# openmv.net
KiCad netlist of a schematic drawn in EAGLE
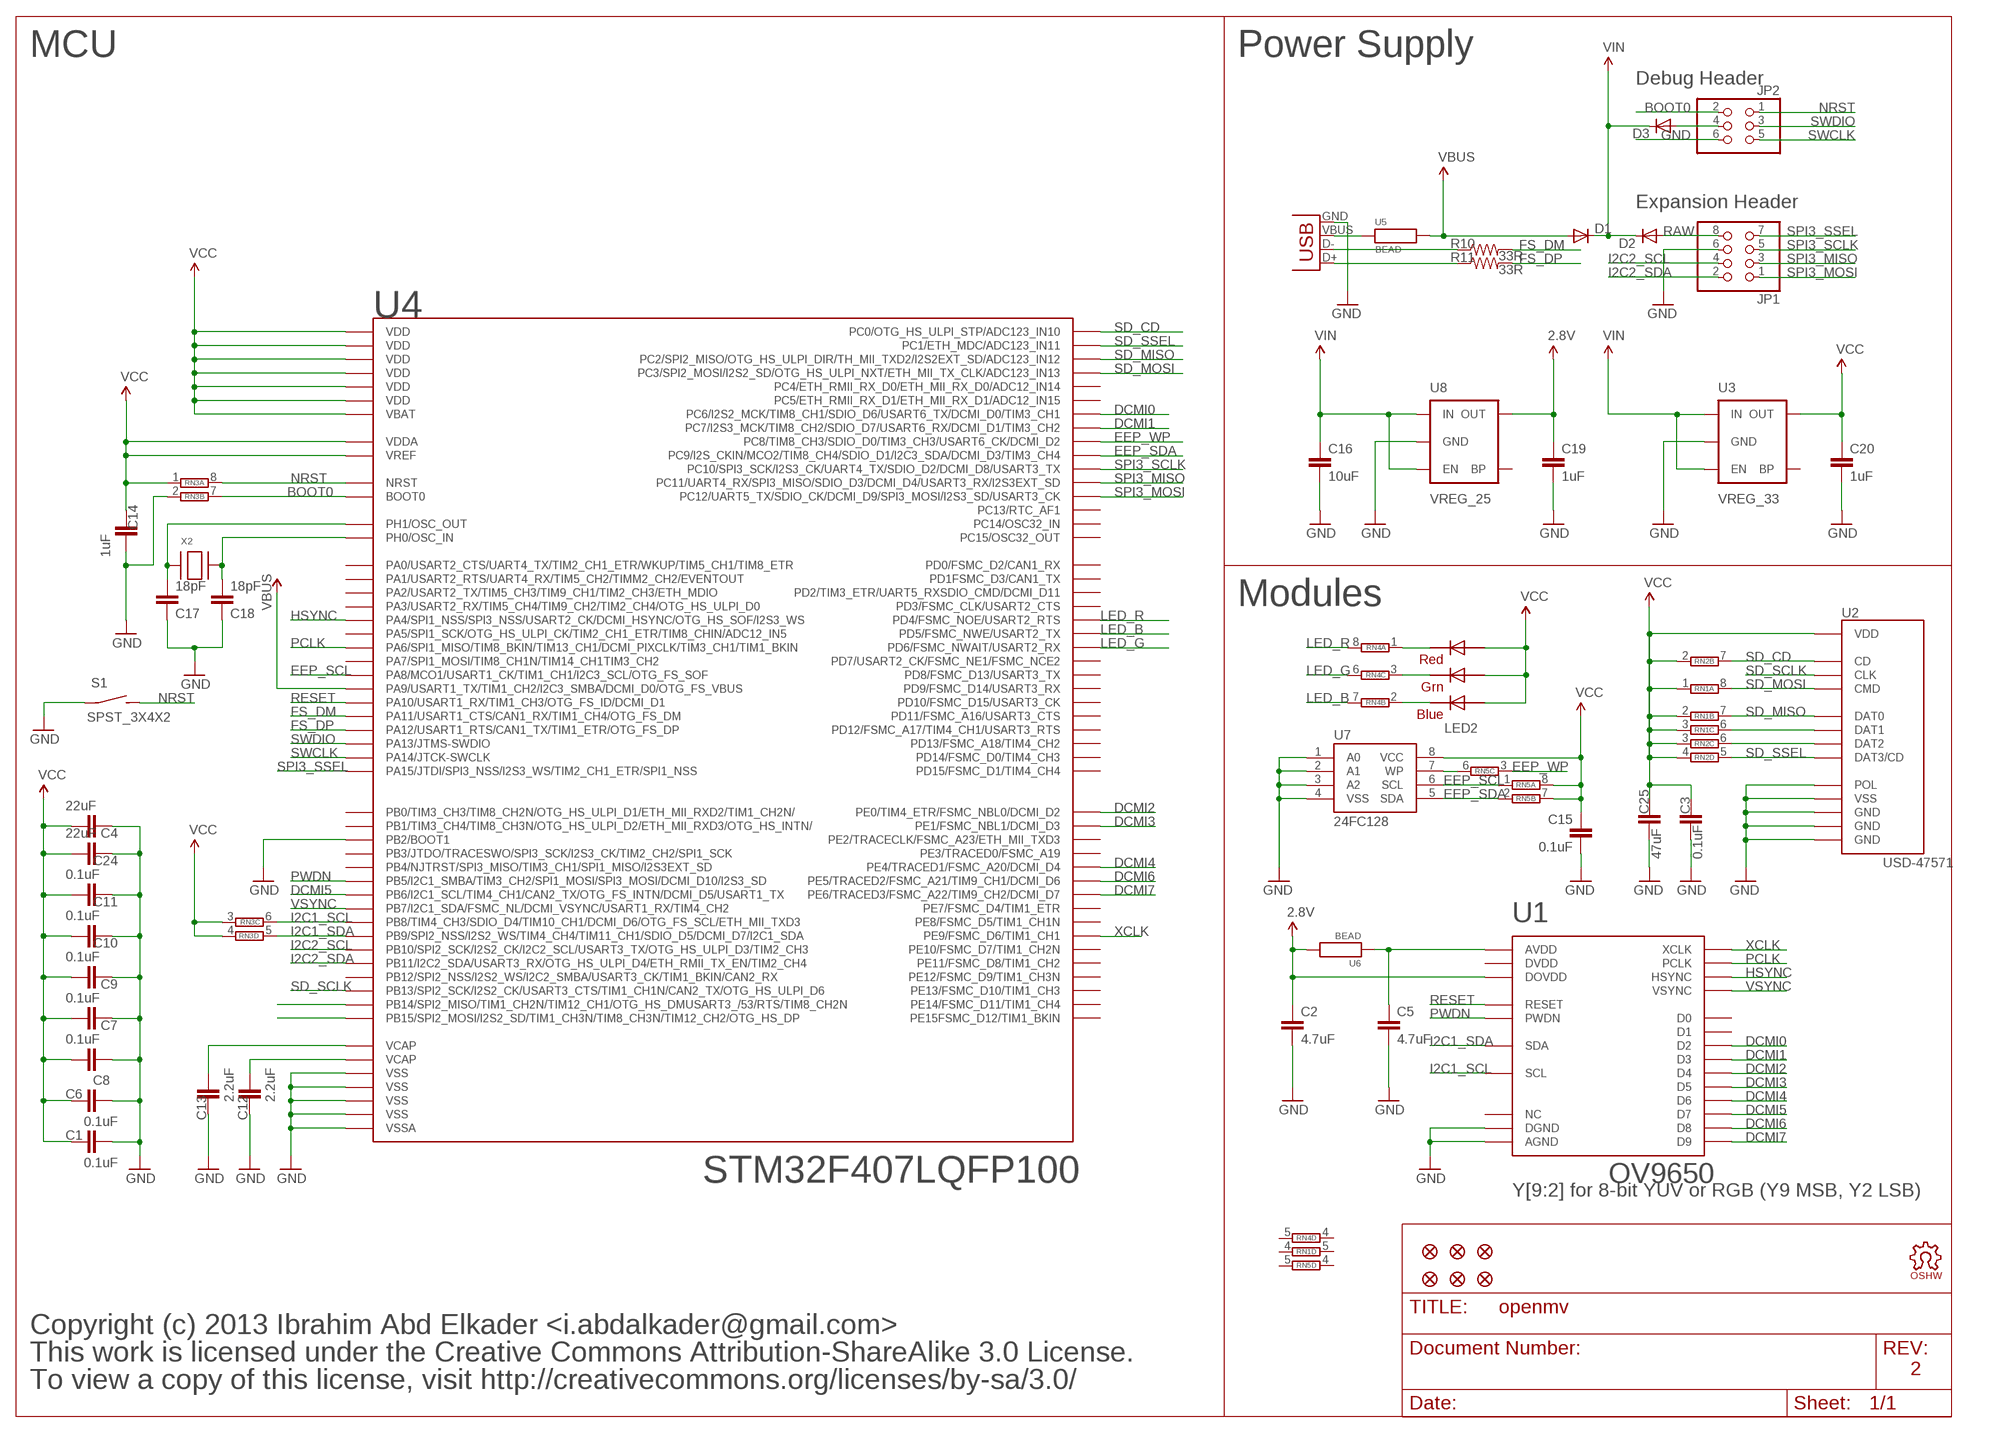
[diagram p0: schematic, sheet 1]

(export (version "E")
  (design (tool "Eeschema 10.0.6"))
  (components
    (comp (ref "C1")
      (value "0.1uF")
      (footprint "eagle-import:0402-CAP")
      (libsource (lib "eagle-import") (part "CAP0402-CAP"))
    )
    (comp (ref "C2")
      (value "4.7uF")
      (footprint "eagle-import:0402-CAP")
      (libsource (lib "eagle-import") (part "CAP0402-CAP"))
    )
    (comp (ref "C3")
      (value "0.1uF")
      (footprint "eagle-import:0402-CAP")
      (libsource (lib "eagle-import") (part "CAP0402-CAP"))
    )
    (comp (ref "C4")
      (value "22uF")
      (footprint "eagle-import:0805")
      (libsource (lib "eagle-import") (part "CAP0805"))
    )
    (comp (ref "C5")
      (value "4.7uF")
      (footprint "eagle-import:0402-CAP")
      (libsource (lib "eagle-import") (part "CAP0402-CAP"))
    )
    (comp (ref "C6")
      (value "0.1uF")
      (footprint "eagle-import:0402-CAP")
      (libsource (lib "eagle-import") (part "CAP0402-CAP"))
    )
    (comp (ref "C7")
      (value "0.1uF")
      (footprint "eagle-import:0402-CAP")
      (libsource (lib "eagle-import") (part "CAP0402-CAP"))
    )
    (comp (ref "C8")
      (value "0.1uF")
      (footprint "eagle-import:0402-CAP")
      (libsource (lib "eagle-import") (part "CAP0402-CAP"))
    )
    (comp (ref "C9")
      (value "0.1uF")
      (footprint "eagle-import:0402-CAP")
      (libsource (lib "eagle-import") (part "CAP0402-CAP"))
    )
    (comp (ref "C10")
      (value "0.1uF")
      (footprint "eagle-import:0402-CAP")
      (libsource (lib "eagle-import") (part "CAP0402-CAP"))
    )
    (comp (ref "C11")
      (value "0.1uF")
      (footprint "eagle-import:0402-CAP")
      (libsource (lib "eagle-import") (part "CAP0402-CAP"))
    )
    (comp (ref "C12")
      (value "2.2uF")
      (footprint "eagle-import:0402-CAP")
      (libsource (lib "eagle-import") (part "CAP0402-CAP"))
    )
    (comp (ref "C13")
      (value "2.2uF")
      (footprint "eagle-import:0402-CAP")
      (libsource (lib "eagle-import") (part "CAP0402-CAP"))
    )
    (comp (ref "C14")
      (value "1uF")
      (footprint "eagle-import:0402-CAP")
      (libsource (lib "eagle-import") (part "CAP0402-CAP"))
    )
    (comp (ref "C15")
      (value "0.1uF")
      (footprint "eagle-import:0402-CAP")
      (libsource (lib "eagle-import") (part "CAP0402-CAP"))
    )
    (comp (ref "C16")
      (value "10uF")
      (footprint "eagle-import:0805")
      (libsource (lib "eagle-import") (part "CAP0805"))
    )
    (comp (ref "C17")
      (value "18pF")
      (footprint "eagle-import:0402-CAP")
      (libsource (lib "eagle-import") (part "CAP0402-CAP"))
    )
    (comp (ref "C18")
      (value "18pF")
      (footprint "eagle-import:0402-CAP")
      (libsource (lib "eagle-import") (part "CAP0402-CAP"))
    )
    (comp (ref "C19")
      (value "1uF")
      (footprint "eagle-import:0402-CAP")
      (libsource (lib "eagle-import") (part "CAP0402-CAP"))
    )
    (comp (ref "C20")
      (value "1uF")
      (footprint "eagle-import:0402-CAP")
      (libsource (lib "eagle-import") (part "CAP0402-CAP"))
    )
    (comp (ref "C24")
      (value "22uF")
      (footprint "eagle-import:0805")
      (libsource (lib "eagle-import") (part "CAP0805"))
    )
    (comp (ref "C25")
      (value "47uF")
      (footprint "eagle-import:0805")
      (libsource (lib "eagle-import") (part "CAP0805"))
    )
    (comp (ref "D1")
      (value "DIODESOD")
      (footprint "eagle-import:SOD-323")
      (libsource (lib "eagle-import") (part "DIODESOD"))
    )
    (comp (ref "D2")
      (value "DIODESOD")
      (footprint "eagle-import:SOD-323")
      (libsource (lib "eagle-import") (part "DIODESOD"))
    )
    (comp (ref "D3")
      (value "DIODESOD")
      (footprint "eagle-import:SOD-323")
      (libsource (lib "eagle-import") (part "DIODESOD"))
    )
    (comp (ref "JP1")
      (value "PINHD-2X4")
      (footprint "eagle-import:2X04")
      (libsource (lib "eagle-import") (part "PINHD-2X4"))
    )
    (comp (ref "JP2")
      (value "PINHD-2X3")
      (footprint "eagle-import:2X03")
      (libsource (lib "eagle-import") (part "PINHD-2X3"))
    )
    (comp (ref "JP3")
      (value "FIDUCIAL1X2")
      (footprint "eagle-import:FIDUCIAL-1X2")
      (libsource (lib "eagle-import") (part "FIDUCIAL1X2"))
    )
    (comp (ref "JP4")
      (value "FIDUCIAL1X2")
      (footprint "eagle-import:FIDUCIAL-1X2")
      (libsource (lib "eagle-import") (part "FIDUCIAL1X2"))
    )
    (comp (ref "JP5")
      (value "FIDUCIAL1X2")
      (footprint "eagle-import:FIDUCIAL-1X2")
      (libsource (lib "eagle-import") (part "FIDUCIAL1X2"))
    )
    (comp (ref "JP6")
      (value "FIDUCIAL1X2")
      (footprint "eagle-import:FIDUCIAL-1X2")
      (libsource (lib "eagle-import") (part "FIDUCIAL1X2"))
    )
    (comp (ref "JP7")
      (value "FIDUCIAL1X2")
      (footprint "eagle-import:FIDUCIAL-1X2")
      (libsource (lib "eagle-import") (part "FIDUCIAL1X2"))
    )
    (comp (ref "JP8")
      (value "FIDUCIAL1X2")
      (footprint "eagle-import:FIDUCIAL-1X2")
      (libsource (lib "eagle-import") (part "FIDUCIAL1X2"))
    )
    (comp (ref "LED2")
      (value "RGBLED5050")
      (footprint "eagle-import:RGBLED5050")
      (libsource (lib "eagle-import") (part "RGBLED5050"))
    )
    (comp (ref "LOGO1")
      (value "OSHW_LOGO_FILLX0150-NT")
      (footprint "eagle-import:OSHW_FILLX150_NOTEXT")
      (libsource (lib "eagle-import") (part "OSHW_LOGO_FILLX0150-NT"))
    )
    (comp (ref "R10")
      (value "33R")
      (footprint "eagle-import:0402-RES")
      (libsource (lib "eagle-import") (part "RESISTOR0402-RES"))
    )
    (comp (ref "R11")
      (value "33R")
      (footprint "eagle-import:0402-RES")
      (libsource (lib "eagle-import") (part "RESISTOR0402-RES"))
    )
    (comp (ref "RN1")
      (value "4R-NCAT16")
      (footprint "eagle-import:CAT16")
      (fields (field (name "OC_FARNELL") "unknown") (field (name "OC_NEWARK") "unknown"))
      (libsource (lib "eagle-import") (part "4R-NCAT16"))
    )
    (comp (ref "RN2")
      (value "4R-NCAT16")
      (footprint "eagle-import:CAT16")
      (fields (field (name "OC_FARNELL") "unknown") (field (name "OC_NEWARK") "unknown"))
      (libsource (lib "eagle-import") (part "4R-NCAT16"))
    )
    (comp (ref "RN3")
      (value "4R-NCAT16")
      (footprint "eagle-import:CAT16")
      (libsource (lib "eagle-import") (part "4R-NCAT16"))
    )
    (comp (ref "RN4")
      (value "4R-NCAT16")
      (footprint "eagle-import:CAT16")
      (fields (field (name "OC_FARNELL") "unknown") (field (name "OC_NEWARK") "unknown"))
      (libsource (lib "eagle-import") (part "4R-NCAT16"))
    )
    (comp (ref "RN5")
      (value "4R-NCAT16")
      (footprint "eagle-import:CAT16")
      (fields (field (name "OC_FARNELL") "unknown") (field (name "OC_NEWARK") "unknown"))
      (libsource (lib "eagle-import") (part "4R-NCAT16"))
    )
    (comp (ref "S1")
      (value "SPST_3X4X2")
      (footprint "eagle-import:3X4X2TACT")
      (libsource (lib "eagle-import") (part "SPST_3X4X2"))
    )
    (comp (ref "U1")
      (value "OV9650")
      (footprint "eagle-import:OV9650")
      (libsource (lib "eagle-import") (part "OV9650"))
    )
    (comp (ref "U2")
      (value "USD-47571")
      (footprint "eagle-import:USD-47571")
      (libsource (lib "eagle-import") (part "USD-47571"))
    )
    (comp (ref "U3")
      (value "VREG_33")
      (footprint "eagle-import:SOT23-5")
      (libsource (lib "eagle-import") (part "V_REG_LDOSMD"))
    )
    (comp (ref "U4")
      (value "STM32F407LQFP100")
      (footprint "eagle-import:LQFP100")
      (libsource (lib "eagle-import") (part "STM32F407LQFP100"))
    )
    (comp (ref "U5")
      (value "BEAD")
      (footprint "eagle-import:0402-CAP")
      (libsource (lib "eagle-import") (part "BEAD"))
    )
    (comp (ref "U6")
      (value "BEAD")
      (footprint "eagle-import:0402-CAP")
      (libsource (lib "eagle-import") (part "BEAD"))
    )
    (comp (ref "U7")
      (value "24FC128")
      (footprint "eagle-import:MSOP8")
      (libsource (lib "eagle-import") (part "24FC128"))
    )
    (comp (ref "U8")
      (value "VREG_25")
      (footprint "eagle-import:SOT23-5")
      (libsource (lib "eagle-import") (part "V_REG_LDOSMD"))
    )
    (comp (ref "X1")
      (value "USB-MICROB")
      (footprint "eagle-import:USB-MICROB")
      (libsource (lib "eagle-import") (part "USB-MICROB"))
    )
    (comp (ref "X2")
      (value "XTALNX5032")
      (footprint "eagle-import:NX5032")
      (libsource (lib "eagle-import") (part "XTALNX5032"))
    )
  )
  (nets
    (net (code "1") (name "/BOOT0") (class "Default")
      (node (ref "JP2") (pin "2") (pinfunction "2_2") (pintype "passive"))
      (node (ref "RN3") (pin "7") (pinfunction "2_7") (pintype "passive"))
      (node (ref "U4") (pin "94") (pinfunction "BOOT0_94") (pintype "bidirectional"))
    )
    (net (code "2") (name "/DCMI0") (class "Default")
      (node (ref "U1") (pin "P$19") (pinfunction "D2_P$19") (pintype "bidirectional"))
      (node (ref "U4") (pin "63") (pinfunction "PC6/I2S2_MCK/TIM8_CH1/SDIO_D6/USART6_TX/DCMI_D0/TIM3_CH1_63") (pintype "bidirectional"))
    )
    (net (code "3") (name "/DCMI1") (class "Default")
      (node (ref "U1") (pin "P$21") (pinfunction "D3_P$21") (pintype "bidirectional"))
      (node (ref "U4") (pin "64") (pinfunction "PC7/I2S3_MCK/TIM8_CH2/SDIO_D7/USART6_RX/DCMI_D1/TIM3_CH2_64") (pintype "bidirectional"))
    )
    (net (code "4") (name "/DCMI2") (class "Default")
      (node (ref "U1") (pin "P$22") (pinfunction "D4_P$22") (pintype "bidirectional"))
      (node (ref "U4") (pin "97") (pinfunction "PE0/TIM4_ETR/FSMC_NBL0/DCMI_D2_97") (pintype "bidirectional"))
    )
    (net (code "5") (name "/DCMI3") (class "Default")
      (node (ref "U1") (pin "P$20") (pinfunction "D5_P$20") (pintype "bidirectional"))
      (node (ref "U4") (pin "98") (pinfunction "PE1/FSMC_NBL1/DCMI_D3_98") (pintype "bidirectional"))
    )
    (net (code "6") (name "/DCMI4") (class "Default")
      (node (ref "U1") (pin "P$18") (pinfunction "D6_P$18") (pintype "bidirectional"))
      (node (ref "U4") (pin "3") (pinfunction "PE4/TRACED1/FSMC_A20/DCMI_D4_3") (pintype "bidirectional"))
    )
    (net (code "7") (name "/DCMI5") (class "Default")
      (node (ref "U1") (pin "P$16") (pinfunction "D7_P$16") (pintype "bidirectional"))
      (node (ref "U4") (pin "92") (pinfunction "PB6/I2C1_SCL/TIM4_CH1/CAN2_TX/OTG_FS_INTN/DCMI_D5/USART1_TX_92") (pintype "bidirectional"))
    )
    (net (code "8") (name "/DCMI6") (class "Default")
      (node (ref "U1") (pin "P$14") (pinfunction "D8_P$14") (pintype "bidirectional"))
      (node (ref "U4") (pin "4") (pinfunction "PE5/TRACED2/FSMC_A21/TIM9_CH1/DCMI_D6_4") (pintype "bidirectional"))
    )
    (net (code "9") (name "/DCMI7") (class "Default")
      (node (ref "U1") (pin "P$12") (pinfunction "D9_P$12") (pintype "bidirectional"))
      (node (ref "U4") (pin "5") (pinfunction "PE6/TRACED3/FSMC_A22/TIM9_CH2/DCMI_D7_5") (pintype "bidirectional"))
    )
    (net (code "10") (name "/EEP_SCL") (class "Default")
      (node (ref "RN5") (pin "1") (pinfunction "1_1") (pintype "passive"))
      (node (ref "U4") (pin "67") (pinfunction "PA8/MCO1/USART1_CK/TIM1_CH1/I2C3_SCL/OTG_FS_SOF_67") (pintype "bidirectional"))
      (node (ref "U7") (pin "6") (pinfunction "SCL_6") (pintype "bidirectional"))
    )
    (net (code "11") (name "/EEP_SDA") (class "Default")
      (node (ref "RN5") (pin "2") (pinfunction "1_2") (pintype "passive"))
      (node (ref "U4") (pin "66") (pinfunction "PC9/I2S_CKIN/MCO2/TIM8_CH4/SDIO_D1/I2C3_SDA/DCMI_D3/TIM3_CH4_66") (pintype "bidirectional"))
      (node (ref "U7") (pin "5") (pinfunction "SDA_5") (pintype "bidirectional"))
    )
    (net (code "12") (name "/EEP_WP") (class "Default")
      (node (ref "RN5") (pin "3") (pinfunction "1_3") (pintype "passive"))
      (node (ref "U4") (pin "65") (pinfunction "PC8/TIM8_CH3/SDIO_D0/TIM3_CH3/USART6_CK/DCMI_D2_65") (pintype "bidirectional"))
    )
    (net (code "13") (name "/FS_DM") (class "Default")
      (node (ref "R10") (pin "2") (pinfunction "2_2") (pintype "passive"))
      (node (ref "U4") (pin "70") (pinfunction "PA11/USART1_CTS/CAN1_RX/TIM1_CH4/OTG_FS_DM_70") (pintype "bidirectional"))
    )
    (net (code "14") (name "/FS_DP") (class "Default")
      (node (ref "R11") (pin "2") (pinfunction "2_2") (pintype "passive"))
      (node (ref "U4") (pin "71") (pinfunction "PA12/USART1_RTS/CAN1_TX/TIM1_ETR/OTG_FS_DP_71") (pintype "bidirectional"))
    )
    (net (code "15") (name "/HSYNC") (class "Default")
      (node (ref "U1") (pin "P$9") (pinfunction "HSYNC_P$9") (pintype "bidirectional"))
      (node (ref "U4") (pin "29") (pinfunction "PA4/SPI1_NSS/SPI3_NSS/USART2_CK/DCMI_HSYNC/OTG_HS_SOF/I2S3_WS_29") (pintype "bidirectional"))
    )
    (net (code "16") (name "/I2C1_SCL") (class "Default")
      (node (ref "RN3") (pin "6") (pinfunction "2_6") (pintype "passive"))
      (node (ref "U1") (pin "P$5") (pinfunction "SCL_P$5") (pintype "bidirectional"))
      (node (ref "U4") (pin "95") (pinfunction "PB8/TIM4_CH3/SDIO_D4/TIM10_CH1/DCMI_D6/OTG_FS_SCL/ETH_MII_TXD3_95") (pintype "bidirectional"))
    )
    (net (code "17") (name "/I2C1_SDA") (class "Default")
      (node (ref "RN3") (pin "5") (pinfunction "2_5") (pintype "passive"))
      (node (ref "U1") (pin "P$3") (pinfunction "SDA_P$3") (pintype "bidirectional"))
      (node (ref "U4") (pin "96") (pinfunction "PB9/SPI2_NSS/I2S2_WS/TIM4_CH4/TIM11_CH1/SDIO_D5/DCMI_D7/I2C1_SDA_96") (pintype "bidirectional"))
    )
    (net (code "18") (name "/I2C2_SCL") (class "Default")
      (node (ref "JP1") (pin "4") (pinfunction "4_4") (pintype "passive"))
      (node (ref "U4") (pin "47") (pinfunction "PB10/SPI2_SCK/I2S2_CK/I2C2_SCL/USART3_TX/OTG_HS_ULPI_D3/TIM2_CH3_47") (pintype "bidirectional"))
    )
    (net (code "19") (name "/I2C2_SDA") (class "Default")
      (node (ref "JP1") (pin "2") (pinfunction "2_2") (pintype "passive"))
      (node (ref "U4") (pin "48") (pinfunction "PB11/I2C2_SDA/USART3_RX/OTG_HS_ULPI_D4/ETH_RMII_TX_EN/TIM2_CH4_48") (pintype "bidirectional"))
    )
    (net (code "20") (name "/LED_B") (class "Default")
      (node (ref "RN4") (pin "7") (pinfunction "2_7") (pintype "passive"))
      (node (ref "U4") (pin "86") (pinfunction "PD5/FSMC_NWE/USART2_TX_86") (pintype "bidirectional"))
    )
    (net (code "21") (name "/LED_G") (class "Default")
      (node (ref "RN4") (pin "6") (pinfunction "2_6") (pintype "passive"))
      (node (ref "U4") (pin "87") (pinfunction "PD6/FSMC_NWAIT/USART2_RX_87") (pintype "bidirectional"))
    )
    (net (code "22") (name "/LED_R") (class "Default")
      (node (ref "RN4") (pin "8") (pinfunction "2_8") (pintype "passive"))
      (node (ref "U4") (pin "85") (pinfunction "PD4/FSMC_NOE/USART2_RTS_85") (pintype "bidirectional"))
    )
    (net (code "23") (name "/NRST") (class "Default")
      (node (ref "JP2") (pin "1") (pinfunction "1_1") (pintype "passive"))
      (node (ref "RN3") (pin "8") (pinfunction "2_8") (pintype "passive"))
      (node (ref "S1") (pin "P$2") (pinfunction "S_P$2") (pintype "passive"))
      (node (ref "U4") (pin "14") (pinfunction "NRST_14") (pintype "bidirectional"))
    )
    (net (code "24") (name "/PCLK") (class "Default")
      (node (ref "U1") (pin "P$17") (pinfunction "PCLK_P$17") (pintype "bidirectional"))
      (node (ref "U4") (pin "31") (pinfunction "PA6/SPI1_MISO/TIM8_BKIN/TIM13_CH1/DCMI_PIXCLK/TIM3_CH1/TIM1_BKIN_31") (pintype "bidirectional"))
    )
    (net (code "25") (name "/PWDN") (class "Default")
      (node (ref "U1") (pin "P$8") (pinfunction "PWDN_P$8") (pintype "bidirectional"))
      (node (ref "U4") (pin "91") (pinfunction "PB5/I2C1_SMBA/TIM3_CH2/SPI1_MOSI/SPI3_MOSI/DCMI_D10/I2S3_SD_91") (pintype "bidirectional"))
    )
    (net (code "26") (name "/RAW") (class "Default")
      (node (ref "D2") (pin "2") (pinfunction "A_2") (pintype "passive"))
      (node (ref "JP1") (pin "8") (pinfunction "8_8") (pintype "passive"))
    )
    (net (code "27") (name "/RESET") (class "Default")
      (node (ref "U1") (pin "P$6") (pinfunction "RESET_P$6") (pintype "bidirectional"))
      (node (ref "U4") (pin "69") (pinfunction "PA10/USART1_RX/TIM1_CH3/OTG_FS_ID/DCMI_D1_69") (pintype "bidirectional"))
    )
    (net (code "28") (name "/SD_CD") (class "Default")
      (node (ref "RN2") (pin "7") (pinfunction "2_7") (pintype "passive"))
      (node (ref "U2") (pin "G$5") (pinfunction "CD_G$5") (pintype "power_in"))
      (node (ref "U4") (pin "15") (pinfunction "PC0/OTG_HS_ULPI_STP/ADC123_IN10_15") (pintype "bidirectional"))
    )
    (net (code "29") (name "/SD_MISO") (class "Default")
      (node (ref "RN1") (pin "7") (pinfunction "2_7") (pintype "passive"))
      (node (ref "U2") (pin "P$7") (pinfunction "DAT0_P$7") (pintype "bidirectional"))
      (node (ref "U4") (pin "17") (pinfunction "PC2/SPI2_MISO/OTG_HS_ULPI_DIR/TH_MII_TXD2/I2S2EXT_SD/ADC123_IN12_17") (pintype "bidirectional"))
    )
    (net (code "30") (name "/SD_MOSI") (class "Default")
      (node (ref "RN1") (pin "8") (pinfunction "2_8") (pintype "passive"))
      (node (ref "U2") (pin "P$3") (pinfunction "CMD_P$3") (pintype "bidirectional"))
      (node (ref "U4") (pin "18") (pinfunction "PC3/SPI2_MOSI/I2S2_SD/OTG_HS_ULPI_NXT/ETH_MII_TX_CLK/ADC123_IN13_18") (pintype "bidirectional"))
    )
    (net (code "31") (name "/SD_SCLK") (class "Default")
      (node (ref "U2") (pin "P$5") (pinfunction "CLK_P$5") (pintype "bidirectional"))
      (node (ref "U4") (pin "52") (pinfunction "PB13/SPI2_SCK/I2S2_CK/USART3_CTS/TIM1_CH1N/CAN2_TX/OTG_HS_ULPI_D6_52") (pintype "bidirectional"))
    )
    (net (code "32") (name "/SD_SSEL") (class "Default")
      (node (ref "RN2") (pin "5") (pinfunction "2_5") (pintype "passive"))
      (node (ref "U2") (pin "P$2") (pinfunction "DAT3/CD_P$2") (pintype "bidirectional"))
      (node (ref "U4") (pin "16") (pinfunction "PC1/ETH_MDC/ADC123_IN11_16") (pintype "bidirectional"))
    )
    (net (code "33") (name "/SPI3_MISO") (class "Default")
      (node (ref "JP1") (pin "3") (pinfunction "3_3") (pintype "passive"))
      (node (ref "U4") (pin "79") (pinfunction "PC11/UART4_RX/SPI3_MISO/SDIO_D3/DCMI_D4/USART3_RX/I2S3EXT_SD_79") (pintype "bidirectional"))
    )
    (net (code "34") (name "/SPI3_MOSI") (class "Default")
      (node (ref "JP1") (pin "1") (pinfunction "1_1") (pintype "passive"))
      (node (ref "U4") (pin "80") (pinfunction "PC12/UART5_TX/SDIO_CK/DCMI_D9/SPI3_MOSI/I2S3_SD/USART3_CK_80") (pintype "bidirectional"))
    )
    (net (code "35") (name "/SPI3_SCLK") (class "Default")
      (node (ref "JP1") (pin "5") (pinfunction "5_5") (pintype "passive"))
      (node (ref "U4") (pin "78") (pinfunction "PC10/SPI3_SCK/I2S3_CK/UART4_TX/SDIO_D2/DCMI_D8/USART3_TX_78") (pintype "bidirectional"))
    )
    (net (code "36") (name "/SPI3_SSEL") (class "Default")
      (node (ref "JP1") (pin "7") (pinfunction "7_7") (pintype "passive"))
      (node (ref "U4") (pin "77") (pinfunction "PA15/JTDI/SPI3_NSS/I2S3_WS/TIM2_CH1_ETR/SPI1_NSS_77") (pintype "bidirectional"))
    )
    (net (code "37") (name "/SWCLK") (class "Default")
      (node (ref "JP2") (pin "5") (pinfunction "5_5") (pintype "passive"))
      (node (ref "U4") (pin "76") (pinfunction "PA14/JTCK-SWCLK_76") (pintype "bidirectional"))
    )
    (net (code "38") (name "/SWDIO") (class "Default")
      (node (ref "JP2") (pin "3") (pinfunction "3_3") (pintype "passive"))
      (node (ref "U4") (pin "72") (pinfunction "PA13/JTMS-SWDIO_72") (pintype "bidirectional"))
    )
    (net (code "39") (name "/VSYNC") (class "Default")
      (node (ref "U1") (pin "P$7") (pinfunction "VSYNC_P$7") (pintype "bidirectional"))
      (node (ref "U4") (pin "93") (pinfunction "PB7/I2C1_SDA/FSMC_NL/DCMI_VSYNC/USART1_RX/TIM4_CH2_93") (pintype "bidirectional"))
    )
    (net (code "40") (name "/XCLK") (class "Default")
      (node (ref "U1") (pin "P$13") (pinfunction "XCLK_P$13") (pintype "bidirectional"))
      (node (ref "U4") (pin "40") (pinfunction "PE9/FSMC_D6/TIM1_CH1_40") (pintype "bidirectional"))
    )
    (net (code "41") (name "2.8V") (class "Default")
      (node (ref "C19") (pin "1") (pinfunction "1_1") (pintype "passive"))
      (node (ref "C2") (pin "1") (pinfunction "1_1") (pintype "passive"))
      (node (ref "U1") (pin "P$11") (pinfunction "DOVDD_P$11") (pintype "bidirectional"))
      (node (ref "U6") (pin "2") (pinfunction "2_2") (pintype "passive"))
      (node (ref "U8") (pin "5") (pinfunction "OUT_5") (pintype "passive"))
    )
    (net (code "42") (name "GND") (class "Default")
      (node (ref "C1") (pin "1") (pinfunction "1_1") (pintype "passive"))
      (node (ref "C10") (pin "2") (pinfunction "2_2") (pintype "passive"))
      (node (ref "C11") (pin "2") (pinfunction "2_2") (pintype "passive"))
      (node (ref "C12") (pin "2") (pinfunction "2_2") (pintype "passive"))
      (node (ref "C13") (pin "2") (pinfunction "2_2") (pintype "passive"))
      (node (ref "C14") (pin "1") (pinfunction "1_1") (pintype "passive"))
      (node (ref "C15") (pin "2") (pinfunction "2_2") (pintype "passive"))
      (node (ref "C16") (pin "2") (pinfunction "2_2") (pintype "passive"))
      (node (ref "C17") (pin "1") (pinfunction "1_1") (pintype "passive"))
      (node (ref "C18") (pin "1") (pinfunction "1_1") (pintype "passive"))
      (node (ref "C19") (pin "2") (pinfunction "2_2") (pintype "passive"))
      (node (ref "C2") (pin "2") (pinfunction "2_2") (pintype "passive"))
      (node (ref "C20") (pin "2") (pinfunction "2_2") (pintype "passive"))
      (node (ref "C24") (pin "1") (pinfunction "1_1") (pintype "passive"))
      (node (ref "C25") (pin "2") (pinfunction "2_2") (pintype "passive"))
      (node (ref "C3") (pin "2") (pinfunction "2_2") (pintype "passive"))
      (node (ref "C4") (pin "1") (pinfunction "1_1") (pintype "passive"))
      (node (ref "C5") (pin "2") (pinfunction "2_2") (pintype "passive"))
      (node (ref "C6") (pin "1") (pinfunction "1_1") (pintype "passive"))
      (node (ref "C7") (pin "2") (pinfunction "2_2") (pintype "passive"))
      (node (ref "C8") (pin "1") (pinfunction "1_1") (pintype "passive"))
      (node (ref "C9") (pin "2") (pinfunction "2_2") (pintype "passive"))
      (node (ref "JP1") (pin "6") (pinfunction "6_6") (pintype "passive"))
      (node (ref "JP2") (pin "6") (pinfunction "6_6") (pintype "passive"))
      (node (ref "RN3") (pin "2") (pinfunction "1_2") (pintype "passive"))
      (node (ref "S1") (pin "P$1") (pinfunction "P_P$1") (pintype "passive"))
      (node (ref "U1") (pin "P$15") (pinfunction "DGND_P$15") (pintype "bidirectional"))
      (node (ref "U1") (pin "P$2") (pinfunction "AGND_P$2") (pintype "power_in"))
      (node (ref "U2") (pin "G$1") (pinfunction "GND_G$1") (pintype "power_in"))
      (node (ref "U2") (pin "G$2") (pinfunction "GND_G$2") (pintype "power_in"))
      (node (ref "U2") (pin "G$3") (pinfunction "GND_G$3") (pintype "power_in"))
      (node (ref "U2") (pin "G$4") (pinfunction "POL_G$4") (pintype "power_in"))
      (node (ref "U2") (pin "P$6") (pinfunction "VSS_P$6") (pintype "power_in"))
      (node (ref "U3") (pin "2") (pinfunction "GND_2") (pintype "input"))
      (node (ref "U4") (pin "10") (pinfunction "VSS_10") (pintype "power_in"))
      (node (ref "U4") (pin "20") (pinfunction "VSSA_20") (pintype "power_in"))
      (node (ref "U4") (pin "27") (pinfunction "VSS_27") (pintype "power_in"))
      (node (ref "U4") (pin "37") (pinfunction "PB2/BOOT1_37") (pintype "bidirectional"))
      (node (ref "U4") (pin "74") (pinfunction "VSS_74") (pintype "power_in"))
      (node (ref "U4") (pin "99") (pinfunction "VSS_99") (pintype "power_in"))
      (node (ref "U7") (pin "1") (pinfunction "A0_1") (pintype "bidirectional"))
      (node (ref "U7") (pin "2") (pinfunction "A1_2") (pintype "bidirectional"))
      (node (ref "U7") (pin "3") (pinfunction "A2_3") (pintype "bidirectional"))
      (node (ref "U7") (pin "4") (pinfunction "VSS_4") (pintype "power_in"))
      (node (ref "U8") (pin "2") (pinfunction "GND_2") (pintype "input"))
      (node (ref "X1") (pin "GND") (pinfunction "GND_GND") (pintype "bidirectional"))
    )
    (net (code "43") (name "Net-(C12-Pad1)") (class "Default")
      (node (ref "C12") (pin "1") (pinfunction "1_1") (pintype "passive"))
      (node (ref "U4") (pin "73") (pinfunction "VCAP_73") (pintype "power_in"))
    )
    (net (code "44") (name "Net-(C13-Pad1)") (class "Default")
      (node (ref "C13") (pin "1") (pinfunction "1_1") (pintype "passive"))
      (node (ref "U4") (pin "49") (pinfunction "VCAP_49") (pintype "power_in"))
    )
    (net (code "45") (name "Net-(D3-A)") (class "Default")
      (node (ref "D3") (pin "2") (pinfunction "A_2") (pintype "passive"))
      (node (ref "JP2") (pin "4") (pinfunction "4_4") (pintype "passive"))
    )
    (net (code "46") (name "Net-(LED2-BLUE_C)") (class "Default")
      (node (ref "LED2") (pin "4") (pinfunction "BLUE_C_4") (pintype "bidirectional"))
      (node (ref "RN4") (pin "2") (pinfunction "1_2") (pintype "passive"))
    )
    (net (code "47") (name "Net-(LED2-GREEN_C)") (class "Default")
      (node (ref "LED2") (pin "6") (pinfunction "GREEN_C_6") (pintype "bidirectional"))
      (node (ref "RN4") (pin "3") (pinfunction "1_3") (pintype "passive"))
    )
    (net (code "48") (name "Net-(LED2-RED_C)") (class "Default")
      (node (ref "LED2") (pin "5") (pinfunction "RED_C_5") (pintype "bidirectional"))
      (node (ref "RN4") (pin "1") (pinfunction "1_1") (pintype "passive"))
    )
    (net (code "49") (name "Net-(R10-Pad1)") (class "Default")
      (node (ref "R10") (pin "1") (pinfunction "1_1") (pintype "passive"))
      (node (ref "X1") (pin "D-") (pinfunction "D-_D-") (pintype "bidirectional"))
    )
    (net (code "50") (name "Net-(R11-Pad1)") (class "Default")
      (node (ref "R11") (pin "1") (pinfunction "1_1") (pintype "passive"))
      (node (ref "X1") (pin "D+") (pinfunction "D+_D+") (pintype "bidirectional"))
    )
    (net (code "51") (name "Net-(RN1C-2)") (class "Default")
      (node (ref "RN1") (pin "6") (pinfunction "2_6") (pintype "passive"))
      (node (ref "U2") (pin "P$8") (pinfunction "DAT1_P$8") (pintype "bidirectional"))
    )
    (net (code "52") (name "Net-(RN2C-2)") (class "Default")
      (node (ref "RN2") (pin "6") (pinfunction "2_6") (pintype "passive"))
      (node (ref "U2") (pin "P$1") (pinfunction "DAT2_P$1") (pintype "bidirectional"))
    )
    (net (code "53") (name "Net-(RN5C-2)") (class "Default")
      (node (ref "RN5") (pin "6") (pinfunction "2_6") (pintype "passive"))
      (node (ref "U7") (pin "7") (pinfunction "WP_7") (pintype "bidirectional"))
    )
    (net (code "54") (name "Net-(U1-AVDD)") (class "Default")
      (node (ref "C5") (pin "1") (pinfunction "1_1") (pintype "passive"))
      (node (ref "U1") (pin "P$4") (pinfunction "AVDD_P$4") (pintype "power_in"))
      (node (ref "U6") (pin "1") (pinfunction "1_1") (pintype "passive"))
    )
    (net (code "55") (name "Net-(U4-PH0{slash}OSC_IN)") (class "Default")
      (node (ref "C18") (pin "2") (pinfunction "2_2") (pintype "passive"))
      (node (ref "U4") (pin "12") (pinfunction "PH0/OSC_IN_12") (pintype "bidirectional"))
      (node (ref "X2") (pin "P$2") (pinfunction "P$2_P$2") (pintype "bidirectional"))
    )
    (net (code "56") (name "Net-(U4-PH1{slash}OSC_OUT)") (class "Default")
      (node (ref "C17") (pin "2") (pinfunction "2_2") (pintype "passive"))
      (node (ref "U4") (pin "13") (pinfunction "PH1/OSC_OUT_13") (pintype "bidirectional"))
      (node (ref "X2") (pin "P$1") (pinfunction "P$1_P$1") (pintype "bidirectional"))
    )
    (net (code "57") (name "Net-(U5-Pad1)") (class "Default")
      (node (ref "U5") (pin "1") (pinfunction "1_1") (pintype "passive"))
      (node (ref "X1") (pin "VBUS") (pinfunction "VBUS_VBUS") (pintype "bidirectional"))
    )
    (net (code "58") (name "VBUS") (class "Default")
      (node (ref "D1") (pin "2") (pinfunction "A_2") (pintype "passive"))
      (node (ref "U4") (pin "68") (pinfunction "PA9/USART1_TX/TIM1_CH2/I2C3_SMBA/DCMI_D0/OTG_FS_VBUS_68") (pintype "bidirectional"))
      (node (ref "U5") (pin "2") (pinfunction "2_2") (pintype "passive"))
    )
    (net (code "59") (name "VCC") (class "Default")
      (node (ref "C1") (pin "2") (pinfunction "2_2") (pintype "passive"))
      (node (ref "C10") (pin "1") (pinfunction "1_1") (pintype "passive"))
      (node (ref "C11") (pin "1") (pinfunction "1_1") (pintype "passive"))
      (node (ref "C14") (pin "2") (pinfunction "2_2") (pintype "passive"))
      (node (ref "C15") (pin "1") (pinfunction "1_1") (pintype "passive"))
      (node (ref "C20") (pin "1") (pinfunction "1_1") (pintype "passive"))
      (node (ref "C24") (pin "2") (pinfunction "2_2") (pintype "passive"))
      (node (ref "C25") (pin "1") (pinfunction "1_1") (pintype "passive"))
      (node (ref "C3") (pin "1") (pinfunction "1_1") (pintype "passive"))
      (node (ref "C4") (pin "2") (pinfunction "2_2") (pintype "passive"))
      (node (ref "C6") (pin "2") (pinfunction "2_2") (pintype "passive"))
      (node (ref "C7") (pin "1") (pinfunction "1_1") (pintype "passive"))
      (node (ref "C8") (pin "2") (pinfunction "2_2") (pintype "passive"))
      (node (ref "C9") (pin "1") (pinfunction "1_1") (pintype "passive"))
      (node (ref "LED2") (pin "1") (pinfunction "GREEN_A_1") (pintype "bidirectional"))
      (node (ref "LED2") (pin "2") (pinfunction "RED_A_2") (pintype "bidirectional"))
      (node (ref "LED2") (pin "3") (pinfunction "BLUE_A_3") (pintype "bidirectional"))
      (node (ref "RN1") (pin "1") (pinfunction "1_1") (pintype "passive"))
      (node (ref "RN1") (pin "2") (pinfunction "1_2") (pintype "passive"))
      (node (ref "RN1") (pin "3") (pinfunction "1_3") (pintype "passive"))
      (node (ref "RN2") (pin "2") (pinfunction "1_2") (pintype "passive"))
      (node (ref "RN2") (pin "3") (pinfunction "1_3") (pintype "passive"))
      (node (ref "RN2") (pin "4") (pinfunction "1_4") (pintype "passive"))
      (node (ref "RN3") (pin "1") (pinfunction "1_1") (pintype "passive"))
      (node (ref "RN3") (pin "3") (pinfunction "1_3") (pintype "passive"))
      (node (ref "RN3") (pin "4") (pinfunction "1_4") (pintype "passive"))
      (node (ref "RN5") (pin "7") (pinfunction "2_7") (pintype "passive"))
      (node (ref "RN5") (pin "8") (pinfunction "2_8") (pintype "passive"))
      (node (ref "U2") (pin "P$4") (pinfunction "VDD_P$4") (pintype "power_in"))
      (node (ref "U3") (pin "5") (pinfunction "OUT_5") (pintype "passive"))
      (node (ref "U4") (pin "100") (pinfunction "VDD_100") (pintype "power_in"))
      (node (ref "U4") (pin "11") (pinfunction "VDD_11") (pintype "power_in"))
      (node (ref "U4") (pin "19") (pinfunction "VDD_19") (pintype "power_in"))
      (node (ref "U4") (pin "21") (pinfunction "VREF_21") (pintype "power_in"))
      (node (ref "U4") (pin "22") (pinfunction "VDDA_22") (pintype "power_in"))
      (node (ref "U4") (pin "28") (pinfunction "VDD_28") (pintype "power_in"))
      (node (ref "U4") (pin "50") (pinfunction "VDD_50") (pintype "power_in"))
      (node (ref "U4") (pin "6") (pinfunction "VBAT_6") (pintype "power_in"))
      (node (ref "U4") (pin "75") (pinfunction "VDD_75") (pintype "power_in"))
      (node (ref "U7") (pin "8") (pinfunction "VCC_8") (pintype "power_in"))
    )
    (net (code "60") (name "VIN") (class "Default")
      (node (ref "C16") (pin "1") (pinfunction "1_1") (pintype "passive"))
      (node (ref "D1") (pin "1") (pinfunction "C_1") (pintype "passive"))
      (node (ref "D2") (pin "1") (pinfunction "C_1") (pintype "passive"))
      (node (ref "D3") (pin "1") (pinfunction "C_1") (pintype "passive"))
      (node (ref "U3") (pin "1") (pinfunction "IN_1") (pintype "input"))
      (node (ref "U3") (pin "3") (pinfunction "EN_3") (pintype "input"))
      (node (ref "U8") (pin "1") (pinfunction "IN_1") (pintype "input"))
      (node (ref "U8") (pin "3") (pinfunction "EN_3") (pintype "input"))
    )
    (net (code "61") (name "unconnected-(RN1D-1-Pad4)") (class "Default")
      (node (ref "RN1") (pin "4") (pinfunction "1_4") (pintype "passive"))
    )
    (net (code "62") (name "unconnected-(RN1D-2-Pad5)") (class "Default")
      (node (ref "RN1") (pin "5") (pinfunction "2_5") (pintype "passive"))
    )
    (net (code "63") (name "unconnected-(RN4D-1-Pad4)") (class "Default")
      (node (ref "RN4") (pin "4") (pinfunction "1_4") (pintype "passive"))
    )
    (net (code "64") (name "unconnected-(RN4D-2-Pad5)") (class "Default")
      (node (ref "RN4") (pin "5") (pinfunction "2_5") (pintype "passive"))
    )
    (net (code "65") (name "unconnected-(RN5D-1-Pad4)") (class "Default")
      (node (ref "RN5") (pin "4") (pinfunction "1_4") (pintype "passive"))
    )
    (net (code "66") (name "unconnected-(RN5D-2-Pad5)") (class "Default")
      (node (ref "RN5") (pin "5") (pinfunction "2_5") (pintype "passive"))
    )
    (net (code "67") (name "unconnected-(U1-D0-PadP$24)") (class "Default")
      (node (ref "U1") (pin "P$24") (pinfunction "D0_P$24") (pintype "bidirectional"))
    )
    (net (code "68") (name "unconnected-(U1-D1-PadP$23)") (class "Default")
      (node (ref "U1") (pin "P$23") (pinfunction "D1_P$23") (pintype "bidirectional"))
    )
    (net (code "69") (name "unconnected-(U1-DVDD-PadP$10)") (class "Default")
      (node (ref "U1") (pin "P$10") (pinfunction "DVDD_P$10") (pintype "bidirectional"))
    )
    (net (code "70") (name "unconnected-(U1-NC-PadP$1)") (class "Default")
      (node (ref "U1") (pin "P$1") (pinfunction "NC_P$1") (pintype "no_connect"))
    )
    (net (code "71") (name "unconnected-(U3-BP-Pad4)") (class "Default")
      (node (ref "U3") (pin "4") (pinfunction "BP_4") (pintype "input"))
    )
    (net (code "72") (name "unconnected-(U4-PA0{slash}USART2_CTS{slash}UART4_TX{slash}TIM2_CH1_ETR{slash}WKUP{slash}TIM5_CH1{slash}TIM8_ETR-Pad23)") (class "Default")
      (node (ref "U4") (pin "23") (pinfunction "PA0/USART2_CTS/UART4_TX/TIM2_CH1_ETR/WKUP/TIM5_CH1/TIM8_ETR_23") (pintype "bidirectional"))
    )
    (net (code "73") (name "unconnected-(U4-PA1{slash}USART2_RTS{slash}UART4_RX{slash}TIM5_CH2{slash}TIMM2_CH2{slash}EVENTOUT-Pad24)") (class "Default")
      (node (ref "U4") (pin "24") (pinfunction "PA1/USART2_RTS/UART4_RX/TIM5_CH2/TIMM2_CH2/EVENTOUT_24") (pintype "bidirectional"))
    )
    (net (code "74") (name "unconnected-(U4-PA2{slash}USART2_TX{slash}TIM5_CH3{slash}TIM9_CH1{slash}TIM2_CH3{slash}ETH_MDIO-Pad25)") (class "Default")
      (node (ref "U4") (pin "25") (pinfunction "PA2/USART2_TX/TIM5_CH3/TIM9_CH1/TIM2_CH3/ETH_MDIO_25") (pintype "bidirectional"))
    )
    (net (code "75") (name "unconnected-(U4-PA3{slash}USART2_RX{slash}TIM5_CH4{slash}TIM9_CH2{slash}TIM2_CH4{slash}OTG_HS_ULPI_D0-Pad26)") (class "Default")
      (node (ref "U4") (pin "26") (pinfunction "PA3/USART2_RX/TIM5_CH4/TIM9_CH2/TIM2_CH4/OTG_HS_ULPI_D0_26") (pintype "bidirectional"))
    )
    (net (code "76") (name "unconnected-(U4-PA5{slash}SPI1_SCK{slash}OTG_HS_ULPI_CK{slash}TIM2_CH1_ETR{slash}TIM8_CHIN{slash}ADC12_IN5-Pad30)") (class "Default")
      (node (ref "U4") (pin "30") (pinfunction "PA5/SPI1_SCK/OTG_HS_ULPI_CK/TIM2_CH1_ETR/TIM8_CHIN/ADC12_IN5_30") (pintype "bidirectional"))
    )
    (net (code "77") (name "unconnected-(U4-PA7{slash}SPI1_MOSI{slash}TIM8_CH1N{slash}TIM14_CH1TIM3_CH2-Pad32)") (class "Default")
      (node (ref "U4") (pin "32") (pinfunction "PA7/SPI1_MOSI/TIM8_CH1N/TIM14_CH1TIM3_CH2_32") (pintype "bidirectional"))
    )
    (net (code "78") (name "unconnected-(U4-PB0{slash}TIM3_CH3{slash}TIM8_CH2N{slash}OTG_HS_ULPI_D1{slash}ETH_MII_RXD2{slash}TIM1_CH2N{slash}-Pad35)") (class "Default")
      (node (ref "U4") (pin "35") (pinfunction "PB0/TIM3_CH3/TIM8_CH2N/OTG_HS_ULPI_D1/ETH_MII_RXD2/TIM1_CH2N/_35") (pintype "bidirectional"))
    )
    (net (code "79") (name "unconnected-(U4-PB1{slash}TIM3_CH4{slash}TIM8_CH3N{slash}OTG_HS_ULPI_D2{slash}ETH_MII_RXD3{slash}OTG_HS_INTN{slash}-Pad36)") (class "Default")
      (node (ref "U4") (pin "36") (pinfunction "PB1/TIM3_CH4/TIM8_CH3N/OTG_HS_ULPI_D2/ETH_MII_RXD3/OTG_HS_INTN/_36") (pintype "bidirectional"))
    )
    (net (code "80") (name "unconnected-(U4-PB3{slash}JTDO{slash}TRACESWO{slash}SPI3_SCK{slash}I2S3_CK{slash}TIM2_CH2{slash}SPI1_SCK-Pad89)") (class "Default")
      (node (ref "U4") (pin "89") (pinfunction "PB3/JTDO/TRACESWO/SPI3_SCK/I2S3_CK/TIM2_CH2/SPI1_SCK_89") (pintype "bidirectional"))
    )
    (net (code "81") (name "unconnected-(U4-PB4{slash}NJTRST{slash}SPI3_MISO{slash}TIM3_CH1{slash}SPI1_MISO{slash}I2S3EXT_SD-Pad90)") (class "Default")
      (node (ref "U4") (pin "90") (pinfunction "PB4/NJTRST/SPI3_MISO/TIM3_CH1/SPI1_MISO/I2S3EXT_SD_90") (pintype "bidirectional"))
    )
    (net (code "82") (name "unconnected-(U4-PB12{slash}SPI2_NSS{slash}I2S2_WS{slash}I2C2_SMBA{slash}USART3_CK{slash}TIM1_BKIN{slash}CAN2_RX-Pad51)") (class "Default")
      (node (ref "U4") (pin "51") (pinfunction "PB12/SPI2_NSS/I2S2_WS/I2C2_SMBA/USART3_CK/TIM1_BKIN/CAN2_RX_51") (pintype "bidirectional"))
    )
    (net (code "83") (name "unconnected-(U4-PB14{slash}SPI2_MISO{slash}TIM1_CH2N{slash}TIM12_CH1{slash}OTG_HS_DMUSART3_{slash}53{slash}RTS{slash}TIM8_CH2N-Pad53)") (class "Default")
      (node (ref "U4") (pin "53") (pinfunction "PB14/SPI2_MISO/TIM1_CH2N/TIM12_CH1/OTG_HS_DMUSART3_/53/RTS/TIM8_CH2N_53") (pintype "bidirectional"))
    )
    (net (code "84") (name "unconnected-(U4-PB15{slash}SPI2_MOSI{slash}I2S2_SD{slash}TIM1_CH3N{slash}TIM8_CH3N{slash}TIM12_CH2{slash}OTG_HS_DP-Pad54)") (class "Default")
      (node (ref "U4") (pin "54") (pinfunction "PB15/SPI2_MOSI/I2S2_SD/TIM1_CH3N/TIM8_CH3N/TIM12_CH2/OTG_HS_DP_54") (pintype "bidirectional"))
    )
    (net (code "85") (name "unconnected-(U4-PC4{slash}ETH_RMII_RX_D0{slash}ETH_MII_RX_D0{slash}ADC12_IN14-Pad33)") (class "Default")
      (node (ref "U4") (pin "33") (pinfunction "PC4/ETH_RMII_RX_D0/ETH_MII_RX_D0/ADC12_IN14_33") (pintype "bidirectional"))
    )
    (net (code "86") (name "unconnected-(U4-PC5{slash}ETH_RMII_RX_D1{slash}ETH_MII_RX_D1{slash}ADC12_IN15-Pad34)") (class "Default")
      (node (ref "U4") (pin "34") (pinfunction "PC5/ETH_RMII_RX_D1/ETH_MII_RX_D1/ADC12_IN15_34") (pintype "bidirectional"))
    )
    (net (code "87") (name "unconnected-(U4-PC13{slash}RTC_AF1-Pad7)") (class "Default")
      (node (ref "U4") (pin "7") (pinfunction "PC13/RTC_AF1_7") (pintype "bidirectional"))
    )
    (net (code "88") (name "unconnected-(U4-PC14{slash}OSC32_IN-Pad8)") (class "Default")
      (node (ref "U4") (pin "8") (pinfunction "PC14/OSC32_IN_8") (pintype "bidirectional"))
    )
    (net (code "89") (name "unconnected-(U4-PC15{slash}OSC32_OUT-Pad9)") (class "Default")
      (node (ref "U4") (pin "9") (pinfunction "PC15/OSC32_OUT_9") (pintype "bidirectional"))
    )
    (net (code "90") (name "unconnected-(U4-PD0{slash}FSMC_D2{slash}CAN1_RX-Pad81)") (class "Default")
      (node (ref "U4") (pin "81") (pinfunction "PD0/FSMC_D2/CAN1_RX_81") (pintype "bidirectional"))
    )
    (net (code "91") (name "unconnected-(U4-PD1FSMC_D3{slash}CAN1_TX-Pad82)") (class "Default")
      (node (ref "U4") (pin "82") (pinfunction "PD1FSMC_D3/CAN1_TX_82") (pintype "bidirectional"))
    )
    (net (code "92") (name "unconnected-(U4-PD2{slash}TIM3_ETR{slash}UART5_RXSDIO_CMD{slash}DCMI_D11-Pad83)") (class "Default")
      (node (ref "U4") (pin "83") (pinfunction "PD2/TIM3_ETR/UART5_RXSDIO_CMD/DCMI_D11_83") (pintype "bidirectional"))
    )
    (net (code "93") (name "unconnected-(U4-PD3{slash}FSMC_CLK{slash}USART2_CTS-Pad84)") (class "Default")
      (node (ref "U4") (pin "84") (pinfunction "PD3/FSMC_CLK/USART2_CTS_84") (pintype "bidirectional"))
    )
    (net (code "94") (name "unconnected-(U4-PD7{slash}USART2_CK{slash}FSMC_NE1{slash}FSMC_NCE2-Pad88)") (class "Default")
      (node (ref "U4") (pin "88") (pinfunction "PD7/USART2_CK/FSMC_NE1/FSMC_NCE2_88") (pintype "bidirectional"))
    )
    (net (code "95") (name "unconnected-(U4-PD8{slash}FSMC_D13{slash}USART3_TX-Pad55)") (class "Default")
      (node (ref "U4") (pin "55") (pinfunction "PD8/FSMC_D13/USART3_TX_55") (pintype "bidirectional"))
    )
    (net (code "96") (name "unconnected-(U4-PD9{slash}FSMC_D14{slash}USART3_RX-Pad56)") (class "Default")
      (node (ref "U4") (pin "56") (pinfunction "PD9/FSMC_D14/USART3_RX_56") (pintype "bidirectional"))
    )
    (net (code "97") (name "unconnected-(U4-PD10{slash}FSMC_D15{slash}USART3_CK-Pad57)") (class "Default")
      (node (ref "U4") (pin "57") (pinfunction "PD10/FSMC_D15/USART3_CK_57") (pintype "bidirectional"))
    )
    (net (code "98") (name "unconnected-(U4-PD11{slash}FSMC_A16{slash}USART3_CTS-Pad58)") (class "Default")
      (node (ref "U4") (pin "58") (pinfunction "PD11/FSMC_A16/USART3_CTS_58") (pintype "bidirectional"))
    )
    (net (code "99") (name "unconnected-(U4-PD12{slash}FSMC_A17{slash}TIM4_CH1{slash}USART3_RTS-Pad59)") (class "Default")
      (node (ref "U4") (pin "59") (pinfunction "PD12/FSMC_A17/TIM4_CH1/USART3_RTS_59") (pintype "bidirectional"))
    )
    (net (code "100") (name "unconnected-(U4-PD13{slash}FSMC_A18{slash}TIM4_CH2-Pad60)") (class "Default")
      (node (ref "U4") (pin "60") (pinfunction "PD13/FSMC_A18/TIM4_CH2_60") (pintype "bidirectional"))
    )
    (net (code "101") (name "unconnected-(U4-PD14{slash}FSMC_D0{slash}TIM4_CH3-Pad61)") (class "Default")
      (node (ref "U4") (pin "61") (pinfunction "PD14/FSMC_D0/TIM4_CH3_61") (pintype "bidirectional"))
    )
    (net (code "102") (name "unconnected-(U4-PD15{slash}FSMC_D1{slash}TIM4_CH4-Pad62)") (class "Default")
      (node (ref "U4") (pin "62") (pinfunction "PD15/FSMC_D1/TIM4_CH4_62") (pintype "bidirectional"))
    )
    (net (code "103") (name "unconnected-(U4-PE2{slash}TRACECLK{slash}FSMC_A23{slash}ETH_MII_TXD3-Pad1)") (class "Default")
      (node (ref "U4") (pin "1") (pinfunction "PE2/TRACECLK/FSMC_A23/ETH_MII_TXD3_1") (pintype "bidirectional"))
    )
    (net (code "104") (name "unconnected-(U4-PE3{slash}TRACED0{slash}FSMC_A19-Pad2)") (class "Default")
      (node (ref "U4") (pin "2") (pinfunction "PE3/TRACED0/FSMC_A19_2") (pintype "bidirectional"))
    )
    (net (code "105") (name "unconnected-(U4-PE7{slash}FSMC_D4{slash}TIM1_ETR-Pad38)") (class "Default")
      (node (ref "U4") (pin "38") (pinfunction "PE7/FSMC_D4/TIM1_ETR_38") (pintype "bidirectional"))
    )
    (net (code "106") (name "unconnected-(U4-PE8{slash}FSMC_D5{slash}TIM1_CH1N-Pad39)") (class "Default")
      (node (ref "U4") (pin "39") (pinfunction "PE8/FSMC_D5/TIM1_CH1N_39") (pintype "bidirectional"))
    )
    (net (code "107") (name "unconnected-(U4-PE10{slash}FSMC_D7{slash}TIM1_CH2N-Pad41)") (class "Default")
      (node (ref "U4") (pin "41") (pinfunction "PE10/FSMC_D7/TIM1_CH2N_41") (pintype "bidirectional"))
    )
    (net (code "108") (name "unconnected-(U4-PE11{slash}FSMC_D8{slash}TIM1_CH2-Pad42)") (class "Default")
      (node (ref "U4") (pin "42") (pinfunction "PE11/FSMC_D8/TIM1_CH2_42") (pintype "bidirectional"))
    )
    (net (code "109") (name "unconnected-(U4-PE12{slash}FSMC_D9{slash}TIM1_CH3N-Pad43)") (class "Default")
      (node (ref "U4") (pin "43") (pinfunction "PE12/FSMC_D9/TIM1_CH3N_43") (pintype "bidirectional"))
    )
    (net (code "110") (name "unconnected-(U4-PE13{slash}FSMC_D10{slash}TIM1_CH3-Pad44)") (class "Default")
      (node (ref "U4") (pin "44") (pinfunction "PE13/FSMC_D10/TIM1_CH3_44") (pintype "bidirectional"))
    )
    (net (code "111") (name "unconnected-(U4-PE14{slash}FSMC_D11{slash}TIM1_CH4-Pad45)") (class "Default")
      (node (ref "U4") (pin "45") (pinfunction "PE14/FSMC_D11/TIM1_CH4_45") (pintype "bidirectional"))
    )
    (net (code "112") (name "unconnected-(U4-PE15FSMC_D12{slash}TIM1_BKIN-Pad46)") (class "Default")
      (node (ref "U4") (pin "46") (pinfunction "PE15FSMC_D12/TIM1_BKIN_46") (pintype "bidirectional"))
    )
    (net (code "113") (name "unconnected-(U8-BP-Pad4)") (class "Default")
      (node (ref "U8") (pin "4") (pinfunction "BP_4") (pintype "input"))
    )
  )
)
